# ledboard.net
KiCad netlist of a schematic drawn in EAGLE
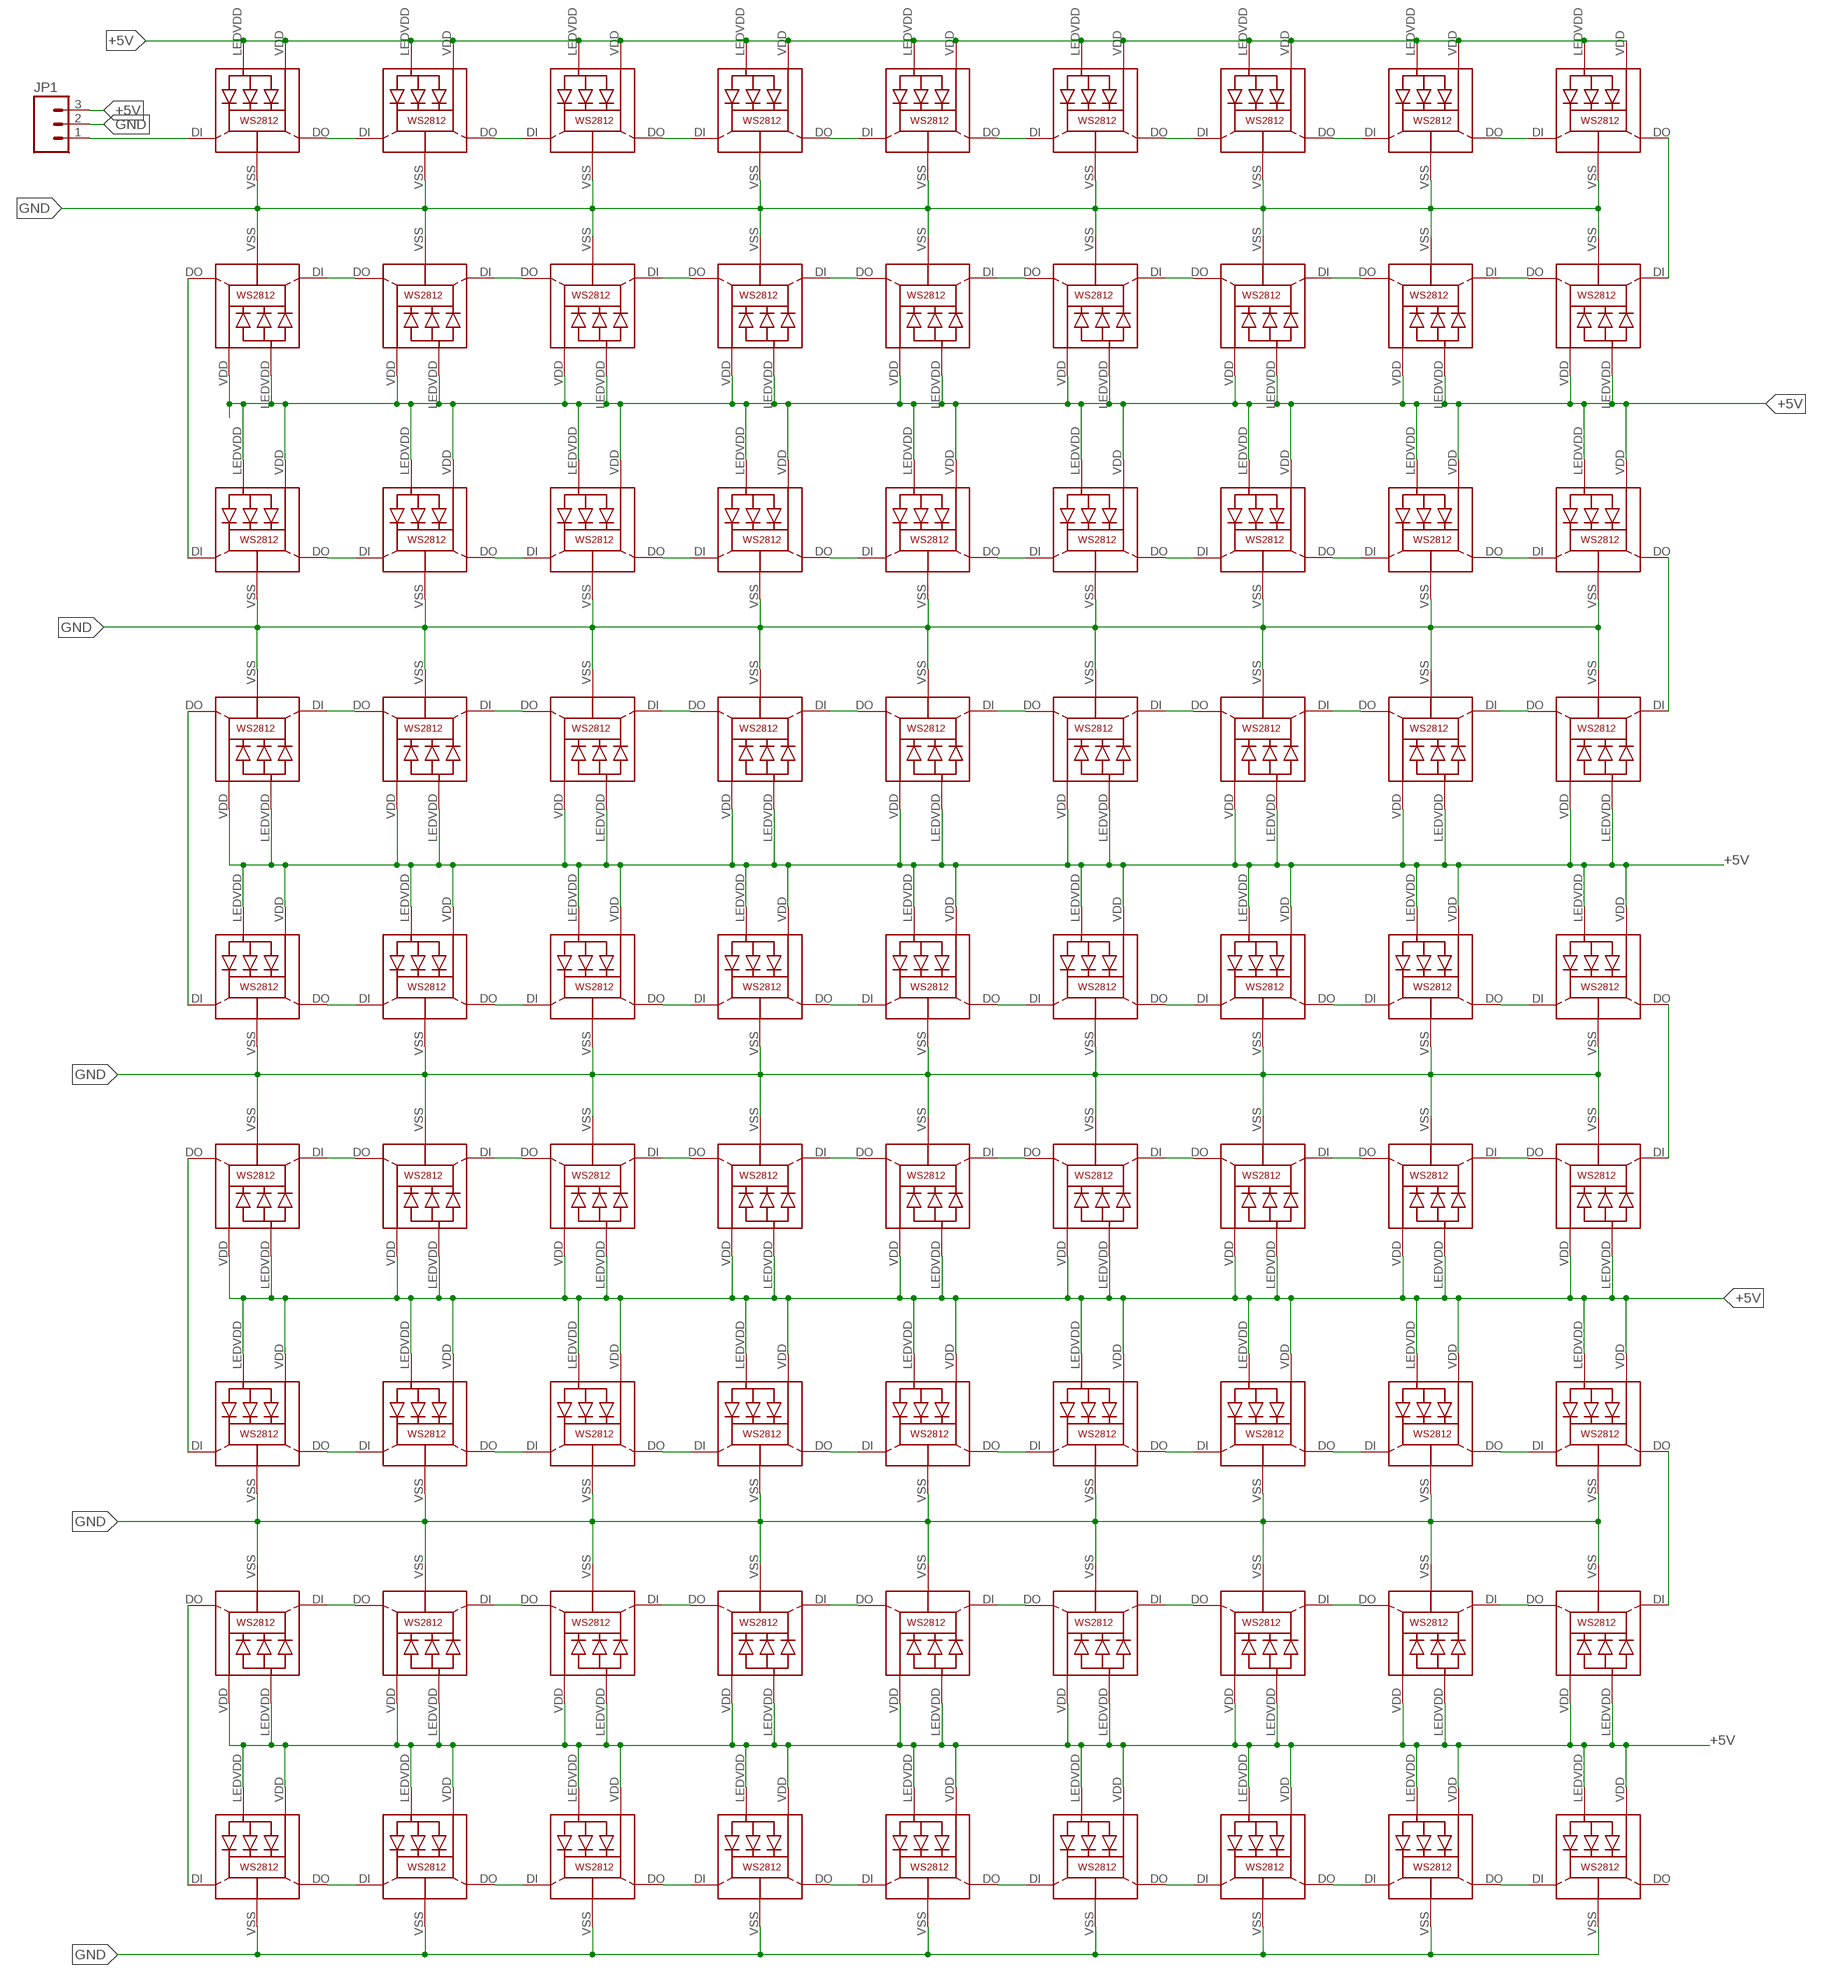
[diagram p0: schematic, sheet 1]

(export (version "E")
  (design (tool "Eeschema 10.0.6"))
  (components
    (comp (ref "JP1")
      (value "M03LONGPADS")
      (footprint "eagle-import:1X03_LONGPADS")
      (libsource (lib "eagle-import") (part "M03LONGPADS"))
    )
    (comp (ref "LEDG00")
      (value "WS2812")
      (footprint "eagle-import:WS2812")
      (libsource (lib "eagle-import") (part "WS2812"))
    )
    (comp (ref "LEDG01")
      (value "WS2812")
      (footprint "eagle-import:WS2812")
      (libsource (lib "eagle-import") (part "WS2812"))
    )
    (comp (ref "LEDG02")
      (value "WS2812")
      (footprint "eagle-import:WS2812")
      (libsource (lib "eagle-import") (part "WS2812"))
    )
    (comp (ref "LEDG03")
      (value "WS2812")
      (footprint "eagle-import:WS2812")
      (libsource (lib "eagle-import") (part "WS2812"))
    )
    (comp (ref "LEDG04")
      (value "WS2812")
      (footprint "eagle-import:WS2812")
      (libsource (lib "eagle-import") (part "WS2812"))
    )
    (comp (ref "LEDG05")
      (value "WS2812")
      (footprint "eagle-import:WS2812")
      (libsource (lib "eagle-import") (part "WS2812"))
    )
    (comp (ref "LEDG06")
      (value "WS2812")
      (footprint "eagle-import:WS2812")
      (libsource (lib "eagle-import") (part "WS2812"))
    )
    (comp (ref "LEDG07")
      (value "WS2812")
      (footprint "eagle-import:WS2812")
      (libsource (lib "eagle-import") (part "WS2812"))
    )
    (comp (ref "LEDG08")
      (value "WS2812")
      (footprint "eagle-import:WS2812")
      (libsource (lib "eagle-import") (part "WS2812"))
    )
    (comp (ref "LEDG10")
      (value "WS2812")
      (footprint "eagle-import:WS2812")
      (libsource (lib "eagle-import") (part "WS2812"))
    )
    (comp (ref "LEDG11")
      (value "WS2812")
      (footprint "eagle-import:WS2812")
      (libsource (lib "eagle-import") (part "WS2812"))
    )
    (comp (ref "LEDG12")
      (value "WS2812")
      (footprint "eagle-import:WS2812")
      (libsource (lib "eagle-import") (part "WS2812"))
    )
    (comp (ref "LEDG13")
      (value "WS2812")
      (footprint "eagle-import:WS2812")
      (libsource (lib "eagle-import") (part "WS2812"))
    )
    (comp (ref "LEDG14")
      (value "WS2812")
      (footprint "eagle-import:WS2812")
      (libsource (lib "eagle-import") (part "WS2812"))
    )
    (comp (ref "LEDG15")
      (value "WS2812")
      (footprint "eagle-import:WS2812")
      (libsource (lib "eagle-import") (part "WS2812"))
    )
    (comp (ref "LEDG16")
      (value "WS2812")
      (footprint "eagle-import:WS2812")
      (libsource (lib "eagle-import") (part "WS2812"))
    )
    (comp (ref "LEDG17")
      (value "WS2812")
      (footprint "eagle-import:WS2812")
      (libsource (lib "eagle-import") (part "WS2812"))
    )
    (comp (ref "LEDG18")
      (value "WS2812")
      (footprint "eagle-import:WS2812")
      (libsource (lib "eagle-import") (part "WS2812"))
    )
    (comp (ref "LEDG20")
      (value "WS2812")
      (footprint "eagle-import:WS2812")
      (libsource (lib "eagle-import") (part "WS2812"))
    )
    (comp (ref "LEDG21")
      (value "WS2812")
      (footprint "eagle-import:WS2812")
      (libsource (lib "eagle-import") (part "WS2812"))
    )
    (comp (ref "LEDG22")
      (value "WS2812")
      (footprint "eagle-import:WS2812")
      (libsource (lib "eagle-import") (part "WS2812"))
    )
    (comp (ref "LEDG23")
      (value "WS2812")
      (footprint "eagle-import:WS2812")
      (libsource (lib "eagle-import") (part "WS2812"))
    )
    (comp (ref "LEDG24")
      (value "WS2812")
      (footprint "eagle-import:WS2812")
      (libsource (lib "eagle-import") (part "WS2812"))
    )
    (comp (ref "LEDG25")
      (value "WS2812")
      (footprint "eagle-import:WS2812")
      (libsource (lib "eagle-import") (part "WS2812"))
    )
    (comp (ref "LEDG26")
      (value "WS2812")
      (footprint "eagle-import:WS2812")
      (libsource (lib "eagle-import") (part "WS2812"))
    )
    (comp (ref "LEDG27")
      (value "WS2812")
      (footprint "eagle-import:WS2812")
      (libsource (lib "eagle-import") (part "WS2812"))
    )
    (comp (ref "LEDG28")
      (value "WS2812")
      (footprint "eagle-import:WS2812")
      (libsource (lib "eagle-import") (part "WS2812"))
    )
    (comp (ref "LEDG30")
      (value "WS2812")
      (footprint "eagle-import:WS2812")
      (libsource (lib "eagle-import") (part "WS2812"))
    )
    (comp (ref "LEDG31")
      (value "WS2812")
      (footprint "eagle-import:WS2812")
      (libsource (lib "eagle-import") (part "WS2812"))
    )
    (comp (ref "LEDG32")
      (value "WS2812")
      (footprint "eagle-import:WS2812")
      (libsource (lib "eagle-import") (part "WS2812"))
    )
    (comp (ref "LEDG33")
      (value "WS2812")
      (footprint "eagle-import:WS2812")
      (libsource (lib "eagle-import") (part "WS2812"))
    )
    (comp (ref "LEDG34")
      (value "WS2812")
      (footprint "eagle-import:WS2812")
      (libsource (lib "eagle-import") (part "WS2812"))
    )
    (comp (ref "LEDG35")
      (value "WS2812")
      (footprint "eagle-import:WS2812")
      (libsource (lib "eagle-import") (part "WS2812"))
    )
    (comp (ref "LEDG36")
      (value "WS2812")
      (footprint "eagle-import:WS2812")
      (libsource (lib "eagle-import") (part "WS2812"))
    )
    (comp (ref "LEDG37")
      (value "WS2812")
      (footprint "eagle-import:WS2812")
      (libsource (lib "eagle-import") (part "WS2812"))
    )
    (comp (ref "LEDG38")
      (value "WS2812")
      (footprint "eagle-import:WS2812")
      (libsource (lib "eagle-import") (part "WS2812"))
    )
    (comp (ref "LEDG40")
      (value "WS2812")
      (footprint "eagle-import:WS2812")
      (libsource (lib "eagle-import") (part "WS2812"))
    )
    (comp (ref "LEDG41")
      (value "WS2812")
      (footprint "eagle-import:WS2812")
      (libsource (lib "eagle-import") (part "WS2812"))
    )
    (comp (ref "LEDG42")
      (value "WS2812")
      (footprint "eagle-import:WS2812")
      (libsource (lib "eagle-import") (part "WS2812"))
    )
    (comp (ref "LEDG43")
      (value "WS2812")
      (footprint "eagle-import:WS2812")
      (libsource (lib "eagle-import") (part "WS2812"))
    )
    (comp (ref "LEDG44")
      (value "WS2812")
      (footprint "eagle-import:WS2812")
      (libsource (lib "eagle-import") (part "WS2812"))
    )
    (comp (ref "LEDG45")
      (value "WS2812")
      (footprint "eagle-import:WS2812")
      (libsource (lib "eagle-import") (part "WS2812"))
    )
    (comp (ref "LEDG46")
      (value "WS2812")
      (footprint "eagle-import:WS2812")
      (libsource (lib "eagle-import") (part "WS2812"))
    )
    (comp (ref "LEDG47")
      (value "WS2812")
      (footprint "eagle-import:WS2812")
      (libsource (lib "eagle-import") (part "WS2812"))
    )
    (comp (ref "LEDG48")
      (value "WS2812")
      (footprint "eagle-import:WS2812")
      (libsource (lib "eagle-import") (part "WS2812"))
    )
    (comp (ref "LEDG50")
      (value "WS2812")
      (footprint "eagle-import:WS2812")
      (libsource (lib "eagle-import") (part "WS2812"))
    )
    (comp (ref "LEDG51")
      (value "WS2812")
      (footprint "eagle-import:WS2812")
      (libsource (lib "eagle-import") (part "WS2812"))
    )
    (comp (ref "LEDG52")
      (value "WS2812")
      (footprint "eagle-import:WS2812")
      (libsource (lib "eagle-import") (part "WS2812"))
    )
    (comp (ref "LEDG53")
      (value "WS2812")
      (footprint "eagle-import:WS2812")
      (libsource (lib "eagle-import") (part "WS2812"))
    )
    (comp (ref "LEDG54")
      (value "WS2812")
      (footprint "eagle-import:WS2812")
      (libsource (lib "eagle-import") (part "WS2812"))
    )
    (comp (ref "LEDG55")
      (value "WS2812")
      (footprint "eagle-import:WS2812")
      (libsource (lib "eagle-import") (part "WS2812"))
    )
    (comp (ref "LEDG56")
      (value "WS2812")
      (footprint "eagle-import:WS2812")
      (libsource (lib "eagle-import") (part "WS2812"))
    )
    (comp (ref "LEDG57")
      (value "WS2812")
      (footprint "eagle-import:WS2812")
      (libsource (lib "eagle-import") (part "WS2812"))
    )
    (comp (ref "LEDG58")
      (value "WS2812")
      (footprint "eagle-import:WS2812")
      (libsource (lib "eagle-import") (part "WS2812"))
    )
    (comp (ref "LEDG60")
      (value "WS2812")
      (footprint "eagle-import:WS2812")
      (libsource (lib "eagle-import") (part "WS2812"))
    )
    (comp (ref "LEDG61")
      (value "WS2812")
      (footprint "eagle-import:WS2812")
      (libsource (lib "eagle-import") (part "WS2812"))
    )
    (comp (ref "LEDG62")
      (value "WS2812")
      (footprint "eagle-import:WS2812")
      (libsource (lib "eagle-import") (part "WS2812"))
    )
    (comp (ref "LEDG63")
      (value "WS2812")
      (footprint "eagle-import:WS2812")
      (libsource (lib "eagle-import") (part "WS2812"))
    )
    (comp (ref "LEDG64")
      (value "WS2812")
      (footprint "eagle-import:WS2812")
      (libsource (lib "eagle-import") (part "WS2812"))
    )
    (comp (ref "LEDG65")
      (value "WS2812")
      (footprint "eagle-import:WS2812")
      (libsource (lib "eagle-import") (part "WS2812"))
    )
    (comp (ref "LEDG66")
      (value "WS2812")
      (footprint "eagle-import:WS2812")
      (libsource (lib "eagle-import") (part "WS2812"))
    )
    (comp (ref "LEDG67")
      (value "WS2812")
      (footprint "eagle-import:WS2812")
      (libsource (lib "eagle-import") (part "WS2812"))
    )
    (comp (ref "LEDG68")
      (value "WS2812")
      (footprint "eagle-import:WS2812")
      (libsource (lib "eagle-import") (part "WS2812"))
    )
    (comp (ref "LEDG70")
      (value "WS2812")
      (footprint "eagle-import:WS2812")
      (libsource (lib "eagle-import") (part "WS2812"))
    )
    (comp (ref "LEDG71")
      (value "WS2812")
      (footprint "eagle-import:WS2812")
      (libsource (lib "eagle-import") (part "WS2812"))
    )
    (comp (ref "LEDG72")
      (value "WS2812")
      (footprint "eagle-import:WS2812")
      (libsource (lib "eagle-import") (part "WS2812"))
    )
    (comp (ref "LEDG73")
      (value "WS2812")
      (footprint "eagle-import:WS2812")
      (libsource (lib "eagle-import") (part "WS2812"))
    )
    (comp (ref "LEDG74")
      (value "WS2812")
      (footprint "eagle-import:WS2812")
      (libsource (lib "eagle-import") (part "WS2812"))
    )
    (comp (ref "LEDG75")
      (value "WS2812")
      (footprint "eagle-import:WS2812")
      (libsource (lib "eagle-import") (part "WS2812"))
    )
    (comp (ref "LEDG76")
      (value "WS2812")
      (footprint "eagle-import:WS2812")
      (libsource (lib "eagle-import") (part "WS2812"))
    )
    (comp (ref "LEDG77")
      (value "WS2812")
      (footprint "eagle-import:WS2812")
      (libsource (lib "eagle-import") (part "WS2812"))
    )
    (comp (ref "LEDG78")
      (value "WS2812")
      (footprint "eagle-import:WS2812")
      (libsource (lib "eagle-import") (part "WS2812"))
    )
    (comp (ref "LEDG80")
      (value "WS2812")
      (footprint "eagle-import:WS2812")
      (libsource (lib "eagle-import") (part "WS2812"))
    )
    (comp (ref "LEDG81")
      (value "WS2812")
      (footprint "eagle-import:WS2812")
      (libsource (lib "eagle-import") (part "WS2812"))
    )
    (comp (ref "LEDG82")
      (value "WS2812")
      (footprint "eagle-import:WS2812")
      (libsource (lib "eagle-import") (part "WS2812"))
    )
    (comp (ref "LEDG83")
      (value "WS2812")
      (footprint "eagle-import:WS2812")
      (libsource (lib "eagle-import") (part "WS2812"))
    )
    (comp (ref "LEDG84")
      (value "WS2812")
      (footprint "eagle-import:WS2812")
      (libsource (lib "eagle-import") (part "WS2812"))
    )
    (comp (ref "LEDG85")
      (value "WS2812")
      (footprint "eagle-import:WS2812")
      (libsource (lib "eagle-import") (part "WS2812"))
    )
    (comp (ref "LEDG86")
      (value "WS2812")
      (footprint "eagle-import:WS2812")
      (libsource (lib "eagle-import") (part "WS2812"))
    )
    (comp (ref "LEDG87")
      (value "WS2812")
      (footprint "eagle-import:WS2812")
      (libsource (lib "eagle-import") (part "WS2812"))
    )
    (comp (ref "LEDG88")
      (value "WS2812")
      (footprint "eagle-import:WS2812")
      (libsource (lib "eagle-import") (part "WS2812"))
    )
  )
  (nets
    (net (code "1") (name "+5V") (class "Default")
      (node (ref "JP1") (pin "3") (pinfunction "3_3") (pintype "passive"))
      (node (ref "LEDG00") (pin "LEDVDD") (pinfunction "LEDVDD_LEDVDD") (pintype "power_in"))
      (node (ref "LEDG00") (pin "VDD") (pinfunction "VDD_VDD") (pintype "power_in"))
      (node (ref "LEDG01") (pin "LEDVDD") (pinfunction "LEDVDD_LEDVDD") (pintype "power_in"))
      (node (ref "LEDG01") (pin "VDD") (pinfunction "VDD_VDD") (pintype "power_in"))
      (node (ref "LEDG02") (pin "LEDVDD") (pinfunction "LEDVDD_LEDVDD") (pintype "power_in"))
      (node (ref "LEDG02") (pin "VDD") (pinfunction "VDD_VDD") (pintype "power_in"))
      (node (ref "LEDG03") (pin "LEDVDD") (pinfunction "LEDVDD_LEDVDD") (pintype "power_in"))
      (node (ref "LEDG03") (pin "VDD") (pinfunction "VDD_VDD") (pintype "power_in"))
      (node (ref "LEDG04") (pin "LEDVDD") (pinfunction "LEDVDD_LEDVDD") (pintype "power_in"))
      (node (ref "LEDG04") (pin "VDD") (pinfunction "VDD_VDD") (pintype "power_in"))
      (node (ref "LEDG05") (pin "LEDVDD") (pinfunction "LEDVDD_LEDVDD") (pintype "power_in"))
      (node (ref "LEDG05") (pin "VDD") (pinfunction "VDD_VDD") (pintype "power_in"))
      (node (ref "LEDG06") (pin "LEDVDD") (pinfunction "LEDVDD_LEDVDD") (pintype "power_in"))
      (node (ref "LEDG06") (pin "VDD") (pinfunction "VDD_VDD") (pintype "power_in"))
      (node (ref "LEDG07") (pin "LEDVDD") (pinfunction "LEDVDD_LEDVDD") (pintype "power_in"))
      (node (ref "LEDG07") (pin "VDD") (pinfunction "VDD_VDD") (pintype "power_in"))
      (node (ref "LEDG08") (pin "LEDVDD") (pinfunction "LEDVDD_LEDVDD") (pintype "power_in"))
      (node (ref "LEDG08") (pin "VDD") (pinfunction "VDD_VDD") (pintype "power_in"))
      (node (ref "LEDG10") (pin "LEDVDD") (pinfunction "LEDVDD_LEDVDD") (pintype "power_in"))
      (node (ref "LEDG10") (pin "VDD") (pinfunction "VDD_VDD") (pintype "power_in"))
      (node (ref "LEDG11") (pin "LEDVDD") (pinfunction "LEDVDD_LEDVDD") (pintype "power_in"))
      (node (ref "LEDG11") (pin "VDD") (pinfunction "VDD_VDD") (pintype "power_in"))
      (node (ref "LEDG12") (pin "LEDVDD") (pinfunction "LEDVDD_LEDVDD") (pintype "power_in"))
      (node (ref "LEDG12") (pin "VDD") (pinfunction "VDD_VDD") (pintype "power_in"))
      (node (ref "LEDG13") (pin "LEDVDD") (pinfunction "LEDVDD_LEDVDD") (pintype "power_in"))
      (node (ref "LEDG13") (pin "VDD") (pinfunction "VDD_VDD") (pintype "power_in"))
      (node (ref "LEDG14") (pin "LEDVDD") (pinfunction "LEDVDD_LEDVDD") (pintype "power_in"))
      (node (ref "LEDG14") (pin "VDD") (pinfunction "VDD_VDD") (pintype "power_in"))
      (node (ref "LEDG15") (pin "LEDVDD") (pinfunction "LEDVDD_LEDVDD") (pintype "power_in"))
      (node (ref "LEDG15") (pin "VDD") (pinfunction "VDD_VDD") (pintype "power_in"))
      (node (ref "LEDG16") (pin "LEDVDD") (pinfunction "LEDVDD_LEDVDD") (pintype "power_in"))
      (node (ref "LEDG16") (pin "VDD") (pinfunction "VDD_VDD") (pintype "power_in"))
      (node (ref "LEDG17") (pin "LEDVDD") (pinfunction "LEDVDD_LEDVDD") (pintype "power_in"))
      (node (ref "LEDG17") (pin "VDD") (pinfunction "VDD_VDD") (pintype "power_in"))
      (node (ref "LEDG18") (pin "LEDVDD") (pinfunction "LEDVDD_LEDVDD") (pintype "power_in"))
      (node (ref "LEDG18") (pin "VDD") (pinfunction "VDD_VDD") (pintype "power_in"))
      (node (ref "LEDG20") (pin "LEDVDD") (pinfunction "LEDVDD_LEDVDD") (pintype "power_in"))
      (node (ref "LEDG20") (pin "VDD") (pinfunction "VDD_VDD") (pintype "power_in"))
      (node (ref "LEDG21") (pin "LEDVDD") (pinfunction "LEDVDD_LEDVDD") (pintype "power_in"))
      (node (ref "LEDG21") (pin "VDD") (pinfunction "VDD_VDD") (pintype "power_in"))
      (node (ref "LEDG22") (pin "LEDVDD") (pinfunction "LEDVDD_LEDVDD") (pintype "power_in"))
      (node (ref "LEDG22") (pin "VDD") (pinfunction "VDD_VDD") (pintype "power_in"))
      (node (ref "LEDG23") (pin "LEDVDD") (pinfunction "LEDVDD_LEDVDD") (pintype "power_in"))
      (node (ref "LEDG23") (pin "VDD") (pinfunction "VDD_VDD") (pintype "power_in"))
      (node (ref "LEDG24") (pin "LEDVDD") (pinfunction "LEDVDD_LEDVDD") (pintype "power_in"))
      (node (ref "LEDG24") (pin "VDD") (pinfunction "VDD_VDD") (pintype "power_in"))
      (node (ref "LEDG25") (pin "LEDVDD") (pinfunction "LEDVDD_LEDVDD") (pintype "power_in"))
      (node (ref "LEDG25") (pin "VDD") (pinfunction "VDD_VDD") (pintype "power_in"))
      (node (ref "LEDG26") (pin "LEDVDD") (pinfunction "LEDVDD_LEDVDD") (pintype "power_in"))
      (node (ref "LEDG26") (pin "VDD") (pinfunction "VDD_VDD") (pintype "power_in"))
      (node (ref "LEDG27") (pin "LEDVDD") (pinfunction "LEDVDD_LEDVDD") (pintype "power_in"))
      (node (ref "LEDG27") (pin "VDD") (pinfunction "VDD_VDD") (pintype "power_in"))
      (node (ref "LEDG28") (pin "LEDVDD") (pinfunction "LEDVDD_LEDVDD") (pintype "power_in"))
      (node (ref "LEDG28") (pin "VDD") (pinfunction "VDD_VDD") (pintype "power_in"))
      (node (ref "LEDG30") (pin "LEDVDD") (pinfunction "LEDVDD_LEDVDD") (pintype "power_in"))
      (node (ref "LEDG30") (pin "VDD") (pinfunction "VDD_VDD") (pintype "power_in"))
      (node (ref "LEDG31") (pin "LEDVDD") (pinfunction "LEDVDD_LEDVDD") (pintype "power_in"))
      (node (ref "LEDG31") (pin "VDD") (pinfunction "VDD_VDD") (pintype "power_in"))
      (node (ref "LEDG32") (pin "LEDVDD") (pinfunction "LEDVDD_LEDVDD") (pintype "power_in"))
      (node (ref "LEDG32") (pin "VDD") (pinfunction "VDD_VDD") (pintype "power_in"))
      (node (ref "LEDG33") (pin "LEDVDD") (pinfunction "LEDVDD_LEDVDD") (pintype "power_in"))
      (node (ref "LEDG33") (pin "VDD") (pinfunction "VDD_VDD") (pintype "power_in"))
      (node (ref "LEDG34") (pin "LEDVDD") (pinfunction "LEDVDD_LEDVDD") (pintype "power_in"))
      (node (ref "LEDG34") (pin "VDD") (pinfunction "VDD_VDD") (pintype "power_in"))
      (node (ref "LEDG35") (pin "LEDVDD") (pinfunction "LEDVDD_LEDVDD") (pintype "power_in"))
      (node (ref "LEDG35") (pin "VDD") (pinfunction "VDD_VDD") (pintype "power_in"))
      (node (ref "LEDG36") (pin "LEDVDD") (pinfunction "LEDVDD_LEDVDD") (pintype "power_in"))
      (node (ref "LEDG36") (pin "VDD") (pinfunction "VDD_VDD") (pintype "power_in"))
      (node (ref "LEDG37") (pin "LEDVDD") (pinfunction "LEDVDD_LEDVDD") (pintype "power_in"))
      (node (ref "LEDG37") (pin "VDD") (pinfunction "VDD_VDD") (pintype "power_in"))
      (node (ref "LEDG38") (pin "LEDVDD") (pinfunction "LEDVDD_LEDVDD") (pintype "power_in"))
      (node (ref "LEDG38") (pin "VDD") (pinfunction "VDD_VDD") (pintype "power_in"))
      (node (ref "LEDG40") (pin "LEDVDD") (pinfunction "LEDVDD_LEDVDD") (pintype "power_in"))
      (node (ref "LEDG40") (pin "VDD") (pinfunction "VDD_VDD") (pintype "power_in"))
      (node (ref "LEDG41") (pin "LEDVDD") (pinfunction "LEDVDD_LEDVDD") (pintype "power_in"))
      (node (ref "LEDG41") (pin "VDD") (pinfunction "VDD_VDD") (pintype "power_in"))
      (node (ref "LEDG42") (pin "LEDVDD") (pinfunction "LEDVDD_LEDVDD") (pintype "power_in"))
      (node (ref "LEDG42") (pin "VDD") (pinfunction "VDD_VDD") (pintype "power_in"))
      (node (ref "LEDG43") (pin "LEDVDD") (pinfunction "LEDVDD_LEDVDD") (pintype "power_in"))
      (node (ref "LEDG43") (pin "VDD") (pinfunction "VDD_VDD") (pintype "power_in"))
      (node (ref "LEDG44") (pin "LEDVDD") (pinfunction "LEDVDD_LEDVDD") (pintype "power_in"))
      (node (ref "LEDG44") (pin "VDD") (pinfunction "VDD_VDD") (pintype "power_in"))
      (node (ref "LEDG45") (pin "LEDVDD") (pinfunction "LEDVDD_LEDVDD") (pintype "power_in"))
      (node (ref "LEDG45") (pin "VDD") (pinfunction "VDD_VDD") (pintype "power_in"))
      (node (ref "LEDG46") (pin "LEDVDD") (pinfunction "LEDVDD_LEDVDD") (pintype "power_in"))
      (node (ref "LEDG46") (pin "VDD") (pinfunction "VDD_VDD") (pintype "power_in"))
      (node (ref "LEDG47") (pin "LEDVDD") (pinfunction "LEDVDD_LEDVDD") (pintype "power_in"))
      (node (ref "LEDG47") (pin "VDD") (pinfunction "VDD_VDD") (pintype "power_in"))
      (node (ref "LEDG48") (pin "LEDVDD") (pinfunction "LEDVDD_LEDVDD") (pintype "power_in"))
      (node (ref "LEDG48") (pin "VDD") (pinfunction "VDD_VDD") (pintype "power_in"))
      (node (ref "LEDG50") (pin "LEDVDD") (pinfunction "LEDVDD_LEDVDD") (pintype "power_in"))
      (node (ref "LEDG50") (pin "VDD") (pinfunction "VDD_VDD") (pintype "power_in"))
      (node (ref "LEDG51") (pin "LEDVDD") (pinfunction "LEDVDD_LEDVDD") (pintype "power_in"))
      (node (ref "LEDG51") (pin "VDD") (pinfunction "VDD_VDD") (pintype "power_in"))
      (node (ref "LEDG52") (pin "LEDVDD") (pinfunction "LEDVDD_LEDVDD") (pintype "power_in"))
      (node (ref "LEDG52") (pin "VDD") (pinfunction "VDD_VDD") (pintype "power_in"))
      (node (ref "LEDG53") (pin "LEDVDD") (pinfunction "LEDVDD_LEDVDD") (pintype "power_in"))
      (node (ref "LEDG53") (pin "VDD") (pinfunction "VDD_VDD") (pintype "power_in"))
      (node (ref "LEDG54") (pin "LEDVDD") (pinfunction "LEDVDD_LEDVDD") (pintype "power_in"))
      (node (ref "LEDG54") (pin "VDD") (pinfunction "VDD_VDD") (pintype "power_in"))
      (node (ref "LEDG55") (pin "LEDVDD") (pinfunction "LEDVDD_LEDVDD") (pintype "power_in"))
      (node (ref "LEDG55") (pin "VDD") (pinfunction "VDD_VDD") (pintype "power_in"))
      (node (ref "LEDG56") (pin "LEDVDD") (pinfunction "LEDVDD_LEDVDD") (pintype "power_in"))
      (node (ref "LEDG56") (pin "VDD") (pinfunction "VDD_VDD") (pintype "power_in"))
      (node (ref "LEDG57") (pin "LEDVDD") (pinfunction "LEDVDD_LEDVDD") (pintype "power_in"))
      (node (ref "LEDG57") (pin "VDD") (pinfunction "VDD_VDD") (pintype "power_in"))
      (node (ref "LEDG58") (pin "LEDVDD") (pinfunction "LEDVDD_LEDVDD") (pintype "power_in"))
      (node (ref "LEDG58") (pin "VDD") (pinfunction "VDD_VDD") (pintype "power_in"))
      (node (ref "LEDG60") (pin "LEDVDD") (pinfunction "LEDVDD_LEDVDD") (pintype "power_in"))
      (node (ref "LEDG60") (pin "VDD") (pinfunction "VDD_VDD") (pintype "power_in"))
      (node (ref "LEDG61") (pin "LEDVDD") (pinfunction "LEDVDD_LEDVDD") (pintype "power_in"))
      (node (ref "LEDG61") (pin "VDD") (pinfunction "VDD_VDD") (pintype "power_in"))
      (node (ref "LEDG62") (pin "LEDVDD") (pinfunction "LEDVDD_LEDVDD") (pintype "power_in"))
      (node (ref "LEDG62") (pin "VDD") (pinfunction "VDD_VDD") (pintype "power_in"))
      (node (ref "LEDG63") (pin "LEDVDD") (pinfunction "LEDVDD_LEDVDD") (pintype "power_in"))
      (node (ref "LEDG63") (pin "VDD") (pinfunction "VDD_VDD") (pintype "power_in"))
      (node (ref "LEDG64") (pin "LEDVDD") (pinfunction "LEDVDD_LEDVDD") (pintype "power_in"))
      (node (ref "LEDG64") (pin "VDD") (pinfunction "VDD_VDD") (pintype "power_in"))
      (node (ref "LEDG65") (pin "LEDVDD") (pinfunction "LEDVDD_LEDVDD") (pintype "power_in"))
      (node (ref "LEDG65") (pin "VDD") (pinfunction "VDD_VDD") (pintype "power_in"))
      (node (ref "LEDG66") (pin "LEDVDD") (pinfunction "LEDVDD_LEDVDD") (pintype "power_in"))
      (node (ref "LEDG66") (pin "VDD") (pinfunction "VDD_VDD") (pintype "power_in"))
      (node (ref "LEDG67") (pin "LEDVDD") (pinfunction "LEDVDD_LEDVDD") (pintype "power_in"))
      (node (ref "LEDG67") (pin "VDD") (pinfunction "VDD_VDD") (pintype "power_in"))
      (node (ref "LEDG68") (pin "LEDVDD") (pinfunction "LEDVDD_LEDVDD") (pintype "power_in"))
      (node (ref "LEDG68") (pin "VDD") (pinfunction "VDD_VDD") (pintype "power_in"))
      (node (ref "LEDG70") (pin "LEDVDD") (pinfunction "LEDVDD_LEDVDD") (pintype "power_in"))
      (node (ref "LEDG70") (pin "VDD") (pinfunction "VDD_VDD") (pintype "power_in"))
      (node (ref "LEDG71") (pin "LEDVDD") (pinfunction "LEDVDD_LEDVDD") (pintype "power_in"))
      (node (ref "LEDG71") (pin "VDD") (pinfunction "VDD_VDD") (pintype "power_in"))
      (node (ref "LEDG72") (pin "LEDVDD") (pinfunction "LEDVDD_LEDVDD") (pintype "power_in"))
      (node (ref "LEDG72") (pin "VDD") (pinfunction "VDD_VDD") (pintype "power_in"))
      (node (ref "LEDG73") (pin "LEDVDD") (pinfunction "LEDVDD_LEDVDD") (pintype "power_in"))
      (node (ref "LEDG73") (pin "VDD") (pinfunction "VDD_VDD") (pintype "power_in"))
      (node (ref "LEDG74") (pin "LEDVDD") (pinfunction "LEDVDD_LEDVDD") (pintype "power_in"))
      (node (ref "LEDG74") (pin "VDD") (pinfunction "VDD_VDD") (pintype "power_in"))
      (node (ref "LEDG75") (pin "LEDVDD") (pinfunction "LEDVDD_LEDVDD") (pintype "power_in"))
      (node (ref "LEDG75") (pin "VDD") (pinfunction "VDD_VDD") (pintype "power_in"))
      (node (ref "LEDG76") (pin "LEDVDD") (pinfunction "LEDVDD_LEDVDD") (pintype "power_in"))
      (node (ref "LEDG76") (pin "VDD") (pinfunction "VDD_VDD") (pintype "power_in"))
      (node (ref "LEDG77") (pin "LEDVDD") (pinfunction "LEDVDD_LEDVDD") (pintype "power_in"))
      (node (ref "LEDG77") (pin "VDD") (pinfunction "VDD_VDD") (pintype "power_in"))
      (node (ref "LEDG78") (pin "LEDVDD") (pinfunction "LEDVDD_LEDVDD") (pintype "power_in"))
      (node (ref "LEDG78") (pin "VDD") (pinfunction "VDD_VDD") (pintype "power_in"))
      (node (ref "LEDG80") (pin "LEDVDD") (pinfunction "LEDVDD_LEDVDD") (pintype "power_in"))
      (node (ref "LEDG80") (pin "VDD") (pinfunction "VDD_VDD") (pintype "power_in"))
      (node (ref "LEDG81") (pin "LEDVDD") (pinfunction "LEDVDD_LEDVDD") (pintype "power_in"))
      (node (ref "LEDG81") (pin "VDD") (pinfunction "VDD_VDD") (pintype "power_in"))
      (node (ref "LEDG82") (pin "LEDVDD") (pinfunction "LEDVDD_LEDVDD") (pintype "power_in"))
      (node (ref "LEDG82") (pin "VDD") (pinfunction "VDD_VDD") (pintype "power_in"))
      (node (ref "LEDG83") (pin "LEDVDD") (pinfunction "LEDVDD_LEDVDD") (pintype "power_in"))
      (node (ref "LEDG83") (pin "VDD") (pinfunction "VDD_VDD") (pintype "power_in"))
      (node (ref "LEDG84") (pin "LEDVDD") (pinfunction "LEDVDD_LEDVDD") (pintype "power_in"))
      (node (ref "LEDG84") (pin "VDD") (pinfunction "VDD_VDD") (pintype "power_in"))
      (node (ref "LEDG85") (pin "LEDVDD") (pinfunction "LEDVDD_LEDVDD") (pintype "power_in"))
      (node (ref "LEDG85") (pin "VDD") (pinfunction "VDD_VDD") (pintype "power_in"))
      (node (ref "LEDG86") (pin "LEDVDD") (pinfunction "LEDVDD_LEDVDD") (pintype "power_in"))
      (node (ref "LEDG86") (pin "VDD") (pinfunction "VDD_VDD") (pintype "power_in"))
      (node (ref "LEDG87") (pin "LEDVDD") (pinfunction "LEDVDD_LEDVDD") (pintype "power_in"))
      (node (ref "LEDG87") (pin "VDD") (pinfunction "VDD_VDD") (pintype "power_in"))
      (node (ref "LEDG88") (pin "LEDVDD") (pinfunction "LEDVDD_LEDVDD") (pintype "power_in"))
      (node (ref "LEDG88") (pin "VDD") (pinfunction "VDD_VDD") (pintype "power_in"))
    )
    (net (code "2") (name "GND") (class "Default")
      (node (ref "JP1") (pin "2") (pinfunction "2_2") (pintype "passive"))
      (node (ref "LEDG00") (pin "VSS") (pinfunction "GND_VSS") (pintype "power_in"))
      (node (ref "LEDG01") (pin "VSS") (pinfunction "GND_VSS") (pintype "power_in"))
      (node (ref "LEDG02") (pin "VSS") (pinfunction "GND_VSS") (pintype "power_in"))
      (node (ref "LEDG03") (pin "VSS") (pinfunction "GND_VSS") (pintype "power_in"))
      (node (ref "LEDG04") (pin "VSS") (pinfunction "GND_VSS") (pintype "power_in"))
      (node (ref "LEDG05") (pin "VSS") (pinfunction "GND_VSS") (pintype "power_in"))
      (node (ref "LEDG06") (pin "VSS") (pinfunction "GND_VSS") (pintype "power_in"))
      (node (ref "LEDG07") (pin "VSS") (pinfunction "GND_VSS") (pintype "power_in"))
      (node (ref "LEDG08") (pin "VSS") (pinfunction "GND_VSS") (pintype "power_in"))
      (node (ref "LEDG10") (pin "VSS") (pinfunction "GND_VSS") (pintype "power_in"))
      (node (ref "LEDG11") (pin "VSS") (pinfunction "GND_VSS") (pintype "power_in"))
      (node (ref "LEDG12") (pin "VSS") (pinfunction "GND_VSS") (pintype "power_in"))
      (node (ref "LEDG13") (pin "VSS") (pinfunction "GND_VSS") (pintype "power_in"))
      (node (ref "LEDG14") (pin "VSS") (pinfunction "GND_VSS") (pintype "power_in"))
      (node (ref "LEDG15") (pin "VSS") (pinfunction "GND_VSS") (pintype "power_in"))
      (node (ref "LEDG16") (pin "VSS") (pinfunction "GND_VSS") (pintype "power_in"))
      (node (ref "LEDG17") (pin "VSS") (pinfunction "GND_VSS") (pintype "power_in"))
      (node (ref "LEDG18") (pin "VSS") (pinfunction "GND_VSS") (pintype "power_in"))
      (node (ref "LEDG20") (pin "VSS") (pinfunction "GND_VSS") (pintype "power_in"))
      (node (ref "LEDG21") (pin "VSS") (pinfunction "GND_VSS") (pintype "power_in"))
      (node (ref "LEDG22") (pin "VSS") (pinfunction "GND_VSS") (pintype "power_in"))
      (node (ref "LEDG23") (pin "VSS") (pinfunction "GND_VSS") (pintype "power_in"))
      (node (ref "LEDG24") (pin "VSS") (pinfunction "GND_VSS") (pintype "power_in"))
      (node (ref "LEDG25") (pin "VSS") (pinfunction "GND_VSS") (pintype "power_in"))
      (node (ref "LEDG26") (pin "VSS") (pinfunction "GND_VSS") (pintype "power_in"))
      (node (ref "LEDG27") (pin "VSS") (pinfunction "GND_VSS") (pintype "power_in"))
      (node (ref "LEDG28") (pin "VSS") (pinfunction "GND_VSS") (pintype "power_in"))
      (node (ref "LEDG30") (pin "VSS") (pinfunction "GND_VSS") (pintype "power_in"))
      (node (ref "LEDG31") (pin "VSS") (pinfunction "GND_VSS") (pintype "power_in"))
      (node (ref "LEDG32") (pin "VSS") (pinfunction "GND_VSS") (pintype "power_in"))
      (node (ref "LEDG33") (pin "VSS") (pinfunction "GND_VSS") (pintype "power_in"))
      (node (ref "LEDG34") (pin "VSS") (pinfunction "GND_VSS") (pintype "power_in"))
      (node (ref "LEDG35") (pin "VSS") (pinfunction "GND_VSS") (pintype "power_in"))
      (node (ref "LEDG36") (pin "VSS") (pinfunction "GND_VSS") (pintype "power_in"))
      (node (ref "LEDG37") (pin "VSS") (pinfunction "GND_VSS") (pintype "power_in"))
      (node (ref "LEDG38") (pin "VSS") (pinfunction "GND_VSS") (pintype "power_in"))
      (node (ref "LEDG40") (pin "VSS") (pinfunction "GND_VSS") (pintype "power_in"))
      (node (ref "LEDG41") (pin "VSS") (pinfunction "GND_VSS") (pintype "power_in"))
      (node (ref "LEDG42") (pin "VSS") (pinfunction "GND_VSS") (pintype "power_in"))
      (node (ref "LEDG43") (pin "VSS") (pinfunction "GND_VSS") (pintype "power_in"))
      (node (ref "LEDG44") (pin "VSS") (pinfunction "GND_VSS") (pintype "power_in"))
      (node (ref "LEDG45") (pin "VSS") (pinfunction "GND_VSS") (pintype "power_in"))
      (node (ref "LEDG46") (pin "VSS") (pinfunction "GND_VSS") (pintype "power_in"))
      (node (ref "LEDG47") (pin "VSS") (pinfunction "GND_VSS") (pintype "power_in"))
      (node (ref "LEDG48") (pin "VSS") (pinfunction "GND_VSS") (pintype "power_in"))
      (node (ref "LEDG50") (pin "VSS") (pinfunction "GND_VSS") (pintype "power_in"))
      (node (ref "LEDG51") (pin "VSS") (pinfunction "GND_VSS") (pintype "power_in"))
      (node (ref "LEDG52") (pin "VSS") (pinfunction "GND_VSS") (pintype "power_in"))
      (node (ref "LEDG53") (pin "VSS") (pinfunction "GND_VSS") (pintype "power_in"))
      (node (ref "LEDG54") (pin "VSS") (pinfunction "GND_VSS") (pintype "power_in"))
      (node (ref "LEDG55") (pin "VSS") (pinfunction "GND_VSS") (pintype "power_in"))
      (node (ref "LEDG56") (pin "VSS") (pinfunction "GND_VSS") (pintype "power_in"))
      (node (ref "LEDG57") (pin "VSS") (pinfunction "GND_VSS") (pintype "power_in"))
      (node (ref "LEDG58") (pin "VSS") (pinfunction "GND_VSS") (pintype "power_in"))
      (node (ref "LEDG60") (pin "VSS") (pinfunction "GND_VSS") (pintype "power_in"))
      (node (ref "LEDG61") (pin "VSS") (pinfunction "GND_VSS") (pintype "power_in"))
      (node (ref "LEDG62") (pin "VSS") (pinfunction "GND_VSS") (pintype "power_in"))
      (node (ref "LEDG63") (pin "VSS") (pinfunction "GND_VSS") (pintype "power_in"))
      (node (ref "LEDG64") (pin "VSS") (pinfunction "GND_VSS") (pintype "power_in"))
      (node (ref "LEDG65") (pin "VSS") (pinfunction "GND_VSS") (pintype "power_in"))
      (node (ref "LEDG66") (pin "VSS") (pinfunction "GND_VSS") (pintype "power_in"))
      (node (ref "LEDG67") (pin "VSS") (pinfunction "GND_VSS") (pintype "power_in"))
      (node (ref "LEDG68") (pin "VSS") (pinfunction "GND_VSS") (pintype "power_in"))
      (node (ref "LEDG70") (pin "VSS") (pinfunction "GND_VSS") (pintype "power_in"))
      (node (ref "LEDG71") (pin "VSS") (pinfunction "GND_VSS") (pintype "power_in"))
      (node (ref "LEDG72") (pin "VSS") (pinfunction "GND_VSS") (pintype "power_in"))
      (node (ref "LEDG73") (pin "VSS") (pinfunction "GND_VSS") (pintype "power_in"))
      (node (ref "LEDG74") (pin "VSS") (pinfunction "GND_VSS") (pintype "power_in"))
      (node (ref "LEDG75") (pin "VSS") (pinfunction "GND_VSS") (pintype "power_in"))
      (node (ref "LEDG76") (pin "VSS") (pinfunction "GND_VSS") (pintype "power_in"))
      (node (ref "LEDG77") (pin "VSS") (pinfunction "GND_VSS") (pintype "power_in"))
      (node (ref "LEDG78") (pin "VSS") (pinfunction "GND_VSS") (pintype "power_in"))
      (node (ref "LEDG80") (pin "VSS") (pinfunction "GND_VSS") (pintype "power_in"))
      (node (ref "LEDG81") (pin "VSS") (pinfunction "GND_VSS") (pintype "power_in"))
      (node (ref "LEDG82") (pin "VSS") (pinfunction "GND_VSS") (pintype "power_in"))
      (node (ref "LEDG83") (pin "VSS") (pinfunction "GND_VSS") (pintype "power_in"))
      (node (ref "LEDG84") (pin "VSS") (pinfunction "GND_VSS") (pintype "power_in"))
      (node (ref "LEDG85") (pin "VSS") (pinfunction "GND_VSS") (pintype "power_in"))
      (node (ref "LEDG86") (pin "VSS") (pinfunction "GND_VSS") (pintype "power_in"))
      (node (ref "LEDG87") (pin "VSS") (pinfunction "GND_VSS") (pintype "power_in"))
      (node (ref "LEDG88") (pin "VSS") (pinfunction "GND_VSS") (pintype "power_in"))
    )
    (net (code "3") (name "Net-(JP1-Pad1)") (class "Default")
      (node (ref "JP1") (pin "1") (pinfunction "1_1") (pintype "passive"))
      (node (ref "LEDG00") (pin "DI") (pinfunction "DI_DI") (pintype "input"))
    )
    (net (code "4") (name "Net-(LEDG00-PadDO)") (class "Default")
      (node (ref "LEDG00") (pin "DO") (pinfunction "DO_DO") (pintype "output"))
      (node (ref "LEDG10") (pin "DI") (pinfunction "DI_DI") (pintype "input"))
    )
    (net (code "5") (name "Net-(LEDG01-PadDI)") (class "Default")
      (node (ref "LEDG01") (pin "DI") (pinfunction "DI_DI") (pintype "input"))
      (node (ref "LEDG11") (pin "DO") (pinfunction "DO_DO") (pintype "output"))
    )
    (net (code "6") (name "Net-(LEDG01-PadDO)") (class "Default")
      (node (ref "LEDG01") (pin "DO") (pinfunction "DO_DO") (pintype "output"))
      (node (ref "LEDG02") (pin "DI") (pinfunction "DI_DI") (pintype "input"))
    )
    (net (code "7") (name "Net-(LEDG02-PadDO)") (class "Default")
      (node (ref "LEDG02") (pin "DO") (pinfunction "DO_DO") (pintype "output"))
      (node (ref "LEDG12") (pin "DI") (pinfunction "DI_DI") (pintype "input"))
    )
    (net (code "8") (name "Net-(LEDG03-PadDI)") (class "Default")
      (node (ref "LEDG03") (pin "DI") (pinfunction "DI_DI") (pintype "input"))
      (node (ref "LEDG13") (pin "DO") (pinfunction "DO_DO") (pintype "output"))
    )
    (net (code "9") (name "Net-(LEDG03-PadDO)") (class "Default")
      (node (ref "LEDG03") (pin "DO") (pinfunction "DO_DO") (pintype "output"))
      (node (ref "LEDG04") (pin "DI") (pinfunction "DI_DI") (pintype "input"))
    )
    (net (code "10") (name "Net-(LEDG04-PadDO)") (class "Default")
      (node (ref "LEDG04") (pin "DO") (pinfunction "DO_DO") (pintype "output"))
      (node (ref "LEDG14") (pin "DI") (pinfunction "DI_DI") (pintype "input"))
    )
    (net (code "11") (name "Net-(LEDG05-PadDI)") (class "Default")
      (node (ref "LEDG05") (pin "DI") (pinfunction "DI_DI") (pintype "input"))
      (node (ref "LEDG15") (pin "DO") (pinfunction "DO_DO") (pintype "output"))
    )
    (net (code "12") (name "Net-(LEDG05-PadDO)") (class "Default")
      (node (ref "LEDG05") (pin "DO") (pinfunction "DO_DO") (pintype "output"))
      (node (ref "LEDG06") (pin "DI") (pinfunction "DI_DI") (pintype "input"))
    )
    (net (code "13") (name "Net-(LEDG06-PadDO)") (class "Default")
      (node (ref "LEDG06") (pin "DO") (pinfunction "DO_DO") (pintype "output"))
      (node (ref "LEDG16") (pin "DI") (pinfunction "DI_DI") (pintype "input"))
    )
    (net (code "14") (name "Net-(LEDG07-PadDI)") (class "Default")
      (node (ref "LEDG07") (pin "DI") (pinfunction "DI_DI") (pintype "input"))
      (node (ref "LEDG17") (pin "DO") (pinfunction "DO_DO") (pintype "output"))
    )
    (net (code "15") (name "Net-(LEDG07-PadDO)") (class "Default")
      (node (ref "LEDG07") (pin "DO") (pinfunction "DO_DO") (pintype "output"))
      (node (ref "LEDG08") (pin "DI") (pinfunction "DI_DI") (pintype "input"))
    )
    (net (code "16") (name "Net-(LEDG08-PadDO)") (class "Default")
      (node (ref "LEDG08") (pin "DO") (pinfunction "DO_DO") (pintype "output"))
      (node (ref "LEDG18") (pin "DI") (pinfunction "DI_DI") (pintype "input"))
    )
    (net (code "17") (name "Net-(LEDG10-PadDO)") (class "Default")
      (node (ref "LEDG10") (pin "DO") (pinfunction "DO_DO") (pintype "output"))
      (node (ref "LEDG20") (pin "DI") (pinfunction "DI_DI") (pintype "input"))
    )
    (net (code "18") (name "Net-(LEDG11-PadDI)") (class "Default")
      (node (ref "LEDG11") (pin "DI") (pinfunction "DI_DI") (pintype "input"))
      (node (ref "LEDG21") (pin "DO") (pinfunction "DO_DO") (pintype "output"))
    )
    (net (code "19") (name "Net-(LEDG12-PadDO)") (class "Default")
      (node (ref "LEDG12") (pin "DO") (pinfunction "DO_DO") (pintype "output"))
      (node (ref "LEDG22") (pin "DI") (pinfunction "DI_DI") (pintype "input"))
    )
    (net (code "20") (name "Net-(LEDG13-PadDI)") (class "Default")
      (node (ref "LEDG13") (pin "DI") (pinfunction "DI_DI") (pintype "input"))
      (node (ref "LEDG23") (pin "DO") (pinfunction "DO_DO") (pintype "output"))
    )
    (net (code "21") (name "Net-(LEDG14-PadDO)") (class "Default")
      (node (ref "LEDG14") (pin "DO") (pinfunction "DO_DO") (pintype "output"))
      (node (ref "LEDG24") (pin "DI") (pinfunction "DI_DI") (pintype "input"))
    )
    (net (code "22") (name "Net-(LEDG15-PadDI)") (class "Default")
      (node (ref "LEDG15") (pin "DI") (pinfunction "DI_DI") (pintype "input"))
      (node (ref "LEDG25") (pin "DO") (pinfunction "DO_DO") (pintype "output"))
    )
    (net (code "23") (name "Net-(LEDG16-PadDO)") (class "Default")
      (node (ref "LEDG16") (pin "DO") (pinfunction "DO_DO") (pintype "output"))
      (node (ref "LEDG26") (pin "DI") (pinfunction "DI_DI") (pintype "input"))
    )
    (net (code "24") (name "Net-(LEDG17-PadDI)") (class "Default")
      (node (ref "LEDG17") (pin "DI") (pinfunction "DI_DI") (pintype "input"))
      (node (ref "LEDG27") (pin "DO") (pinfunction "DO_DO") (pintype "output"))
    )
    (net (code "25") (name "Net-(LEDG18-PadDO)") (class "Default")
      (node (ref "LEDG18") (pin "DO") (pinfunction "DO_DO") (pintype "output"))
      (node (ref "LEDG28") (pin "DI") (pinfunction "DI_DI") (pintype "input"))
    )
    (net (code "26") (name "Net-(LEDG20-PadDO)") (class "Default")
      (node (ref "LEDG20") (pin "DO") (pinfunction "DO_DO") (pintype "output"))
      (node (ref "LEDG30") (pin "DI") (pinfunction "DI_DI") (pintype "input"))
    )
    (net (code "27") (name "Net-(LEDG21-PadDI)") (class "Default")
      (node (ref "LEDG21") (pin "DI") (pinfunction "DI_DI") (pintype "input"))
      (node (ref "LEDG31") (pin "DO") (pinfunction "DO_DO") (pintype "output"))
    )
    (net (code "28") (name "Net-(LEDG22-PadDO)") (class "Default")
      (node (ref "LEDG22") (pin "DO") (pinfunction "DO_DO") (pintype "output"))
      (node (ref "LEDG32") (pin "DI") (pinfunction "DI_DI") (pintype "input"))
    )
    (net (code "29") (name "Net-(LEDG23-PadDI)") (class "Default")
      (node (ref "LEDG23") (pin "DI") (pinfunction "DI_DI") (pintype "input"))
      (node (ref "LEDG33") (pin "DO") (pinfunction "DO_DO") (pintype "output"))
    )
    (net (code "30") (name "Net-(LEDG24-PadDO)") (class "Default")
      (node (ref "LEDG24") (pin "DO") (pinfunction "DO_DO") (pintype "output"))
      (node (ref "LEDG34") (pin "DI") (pinfunction "DI_DI") (pintype "input"))
    )
    (net (code "31") (name "Net-(LEDG25-PadDI)") (class "Default")
      (node (ref "LEDG25") (pin "DI") (pinfunction "DI_DI") (pintype "input"))
      (node (ref "LEDG35") (pin "DO") (pinfunction "DO_DO") (pintype "output"))
    )
    (net (code "32") (name "Net-(LEDG26-PadDO)") (class "Default")
      (node (ref "LEDG26") (pin "DO") (pinfunction "DO_DO") (pintype "output"))
      (node (ref "LEDG36") (pin "DI") (pinfunction "DI_DI") (pintype "input"))
    )
    (net (code "33") (name "Net-(LEDG27-PadDI)") (class "Default")
      (node (ref "LEDG27") (pin "DI") (pinfunction "DI_DI") (pintype "input"))
      (node (ref "LEDG37") (pin "DO") (pinfunction "DO_DO") (pintype "output"))
    )
    (net (code "34") (name "Net-(LEDG28-PadDO)") (class "Default")
      (node (ref "LEDG28") (pin "DO") (pinfunction "DO_DO") (pintype "output"))
      (node (ref "LEDG38") (pin "DI") (pinfunction "DI_DI") (pintype "input"))
    )
    (net (code "35") (name "Net-(LEDG30-PadDO)") (class "Default")
      (node (ref "LEDG30") (pin "DO") (pinfunction "DO_DO") (pintype "output"))
      (node (ref "LEDG40") (pin "DI") (pinfunction "DI_DI") (pintype "input"))
    )
    (net (code "36") (name "Net-(LEDG31-PadDI)") (class "Default")
      (node (ref "LEDG31") (pin "DI") (pinfunction "DI_DI") (pintype "input"))
      (node (ref "LEDG41") (pin "DO") (pinfunction "DO_DO") (pintype "output"))
    )
    (net (code "37") (name "Net-(LEDG32-PadDO)") (class "Default")
      (node (ref "LEDG32") (pin "DO") (pinfunction "DO_DO") (pintype "output"))
      (node (ref "LEDG42") (pin "DI") (pinfunction "DI_DI") (pintype "input"))
    )
    (net (code "38") (name "Net-(LEDG33-PadDI)") (class "Default")
      (node (ref "LEDG33") (pin "DI") (pinfunction "DI_DI") (pintype "input"))
      (node (ref "LEDG43") (pin "DO") (pinfunction "DO_DO") (pintype "output"))
    )
    (net (code "39") (name "Net-(LEDG34-PadDO)") (class "Default")
      (node (ref "LEDG34") (pin "DO") (pinfunction "DO_DO") (pintype "output"))
      (node (ref "LEDG44") (pin "DI") (pinfunction "DI_DI") (pintype "input"))
    )
    (net (code "40") (name "Net-(LEDG35-PadDI)") (class "Default")
      (node (ref "LEDG35") (pin "DI") (pinfunction "DI_DI") (pintype "input"))
      (node (ref "LEDG45") (pin "DO") (pinfunction "DO_DO") (pintype "output"))
    )
    (net (code "41") (name "Net-(LEDG36-PadDO)") (class "Default")
      (node (ref "LEDG36") (pin "DO") (pinfunction "DO_DO") (pintype "output"))
      (node (ref "LEDG46") (pin "DI") (pinfunction "DI_DI") (pintype "input"))
    )
    (net (code "42") (name "Net-(LEDG37-PadDI)") (class "Default")
      (node (ref "LEDG37") (pin "DI") (pinfunction "DI_DI") (pintype "input"))
      (node (ref "LEDG47") (pin "DO") (pinfunction "DO_DO") (pintype "output"))
    )
    (net (code "43") (name "Net-(LEDG38-PadDO)") (class "Default")
      (node (ref "LEDG38") (pin "DO") (pinfunction "DO_DO") (pintype "output"))
      (node (ref "LEDG48") (pin "DI") (pinfunction "DI_DI") (pintype "input"))
    )
    (net (code "44") (name "Net-(LEDG40-PadDO)") (class "Default")
      (node (ref "LEDG40") (pin "DO") (pinfunction "DO_DO") (pintype "output"))
      (node (ref "LEDG50") (pin "DI") (pinfunction "DI_DI") (pintype "input"))
    )
    (net (code "45") (name "Net-(LEDG41-PadDI)") (class "Default")
      (node (ref "LEDG41") (pin "DI") (pinfunction "DI_DI") (pintype "input"))
      (node (ref "LEDG51") (pin "DO") (pinfunction "DO_DO") (pintype "output"))
    )
    (net (code "46") (name "Net-(LEDG42-PadDO)") (class "Default")
      (node (ref "LEDG42") (pin "DO") (pinfunction "DO_DO") (pintype "output"))
      (node (ref "LEDG52") (pin "DI") (pinfunction "DI_DI") (pintype "input"))
    )
    (net (code "47") (name "Net-(LEDG43-PadDI)") (class "Default")
      (node (ref "LEDG43") (pin "DI") (pinfunction "DI_DI") (pintype "input"))
      (node (ref "LEDG53") (pin "DO") (pinfunction "DO_DO") (pintype "output"))
    )
    (net (code "48") (name "Net-(LEDG44-PadDO)") (class "Default")
      (node (ref "LEDG44") (pin "DO") (pinfunction "DO_DO") (pintype "output"))
      (node (ref "LEDG54") (pin "DI") (pinfunction "DI_DI") (pintype "input"))
    )
    (net (code "49") (name "Net-(LEDG45-PadDI)") (class "Default")
      (node (ref "LEDG45") (pin "DI") (pinfunction "DI_DI") (pintype "input"))
      (node (ref "LEDG55") (pin "DO") (pinfunction "DO_DO") (pintype "output"))
    )
    (net (code "50") (name "Net-(LEDG46-PadDO)") (class "Default")
      (node (ref "LEDG46") (pin "DO") (pinfunction "DO_DO") (pintype "output"))
      (node (ref "LEDG56") (pin "DI") (pinfunction "DI_DI") (pintype "input"))
    )
    (net (code "51") (name "Net-(LEDG47-PadDI)") (class "Default")
      (node (ref "LEDG47") (pin "DI") (pinfunction "DI_DI") (pintype "input"))
      (node (ref "LEDG57") (pin "DO") (pinfunction "DO_DO") (pintype "output"))
    )
    (net (code "52") (name "Net-(LEDG48-PadDO)") (class "Default")
      (node (ref "LEDG48") (pin "DO") (pinfunction "DO_DO") (pintype "output"))
      (node (ref "LEDG58") (pin "DI") (pinfunction "DI_DI") (pintype "input"))
    )
    (net (code "53") (name "Net-(LEDG50-PadDO)") (class "Default")
      (node (ref "LEDG50") (pin "DO") (pinfunction "DO_DO") (pintype "output"))
      (node (ref "LEDG60") (pin "DI") (pinfunction "DI_DI") (pintype "input"))
    )
    (net (code "54") (name "Net-(LEDG51-PadDI)") (class "Default")
      (node (ref "LEDG51") (pin "DI") (pinfunction "DI_DI") (pintype "input"))
      (node (ref "LEDG61") (pin "DO") (pinfunction "DO_DO") (pintype "output"))
    )
    (net (code "55") (name "Net-(LEDG52-PadDO)") (class "Default")
      (node (ref "LEDG52") (pin "DO") (pinfunction "DO_DO") (pintype "output"))
      (node (ref "LEDG62") (pin "DI") (pinfunction "DI_DI") (pintype "input"))
    )
    (net (code "56") (name "Net-(LEDG53-PadDI)") (class "Default")
      (node (ref "LEDG53") (pin "DI") (pinfunction "DI_DI") (pintype "input"))
      (node (ref "LEDG63") (pin "DO") (pinfunction "DO_DO") (pintype "output"))
    )
    (net (code "57") (name "Net-(LEDG54-PadDO)") (class "Default")
      (node (ref "LEDG54") (pin "DO") (pinfunction "DO_DO") (pintype "output"))
      (node (ref "LEDG64") (pin "DI") (pinfunction "DI_DI") (pintype "input"))
    )
    (net (code "58") (name "Net-(LEDG55-PadDI)") (class "Default")
      (node (ref "LEDG55") (pin "DI") (pinfunction "DI_DI") (pintype "input"))
      (node (ref "LEDG65") (pin "DO") (pinfunction "DO_DO") (pintype "output"))
    )
    (net (code "59") (name "Net-(LEDG56-PadDO)") (class "Default")
      (node (ref "LEDG56") (pin "DO") (pinfunction "DO_DO") (pintype "output"))
      (node (ref "LEDG66") (pin "DI") (pinfunction "DI_DI") (pintype "input"))
    )
    (net (code "60") (name "Net-(LEDG57-PadDI)") (class "Default")
      (node (ref "LEDG57") (pin "DI") (pinfunction "DI_DI") (pintype "input"))
      (node (ref "LEDG67") (pin "DO") (pinfunction "DO_DO") (pintype "output"))
    )
    (net (code "61") (name "Net-(LEDG58-PadDO)") (class "Default")
      (node (ref "LEDG58") (pin "DO") (pinfunction "DO_DO") (pintype "output"))
      (node (ref "LEDG68") (pin "DI") (pinfunction "DI_DI") (pintype "input"))
    )
    (net (code "62") (name "Net-(LEDG60-PadDO)") (class "Default")
      (node (ref "LEDG60") (pin "DO") (pinfunction "DO_DO") (pintype "output"))
      (node (ref "LEDG70") (pin "DI") (pinfunction "DI_DI") (pintype "input"))
    )
    (net (code "63") (name "Net-(LEDG61-PadDI)") (class "Default")
      (node (ref "LEDG61") (pin "DI") (pinfunction "DI_DI") (pintype "input"))
      (node (ref "LEDG71") (pin "DO") (pinfunction "DO_DO") (pintype "output"))
    )
    (net (code "64") (name "Net-(LEDG62-PadDO)") (class "Default")
      (node (ref "LEDG62") (pin "DO") (pinfunction "DO_DO") (pintype "output"))
      (node (ref "LEDG72") (pin "DI") (pinfunction "DI_DI") (pintype "input"))
    )
    (net (code "65") (name "Net-(LEDG63-PadDI)") (class "Default")
      (node (ref "LEDG63") (pin "DI") (pinfunction "DI_DI") (pintype "input"))
      (node (ref "LEDG73") (pin "DO") (pinfunction "DO_DO") (pintype "output"))
    )
    (net (code "66") (name "Net-(LEDG64-PadDO)") (class "Default")
      (node (ref "LEDG64") (pin "DO") (pinfunction "DO_DO") (pintype "output"))
      (node (ref "LEDG74") (pin "DI") (pinfunction "DI_DI") (pintype "input"))
    )
    (net (code "67") (name "Net-(LEDG65-PadDI)") (class "Default")
      (node (ref "LEDG65") (pin "DI") (pinfunction "DI_DI") (pintype "input"))
      (node (ref "LEDG75") (pin "DO") (pinfunction "DO_DO") (pintype "output"))
    )
    (net (code "68") (name "Net-(LEDG66-PadDO)") (class "Default")
      (node (ref "LEDG66") (pin "DO") (pinfunction "DO_DO") (pintype "output"))
      (node (ref "LEDG76") (pin "DI") (pinfunction "DI_DI") (pintype "input"))
    )
    (net (code "69") (name "Net-(LEDG67-PadDI)") (class "Default")
      (node (ref "LEDG67") (pin "DI") (pinfunction "DI_DI") (pintype "input"))
      (node (ref "LEDG77") (pin "DO") (pinfunction "DO_DO") (pintype "output"))
    )
    (net (code "70") (name "Net-(LEDG68-PadDO)") (class "Default")
      (node (ref "LEDG68") (pin "DO") (pinfunction "DO_DO") (pintype "output"))
      (node (ref "LEDG78") (pin "DI") (pinfunction "DI_DI") (pintype "input"))
    )
    (net (code "71") (name "Net-(LEDG70-PadDO)") (class "Default")
      (node (ref "LEDG70") (pin "DO") (pinfunction "DO_DO") (pintype "output"))
      (node (ref "LEDG80") (pin "DI") (pinfunction "DI_DI") (pintype "input"))
    )
    (net (code "72") (name "Net-(LEDG71-PadDI)") (class "Default")
      (node (ref "LEDG71") (pin "DI") (pinfunction "DI_DI") (pintype "input"))
      (node (ref "LEDG81") (pin "DO") (pinfunction "DO_DO") (pintype "output"))
    )
    (net (code "73") (name "Net-(LEDG72-PadDO)") (class "Default")
      (node (ref "LEDG72") (pin "DO") (pinfunction "DO_DO") (pintype "output"))
      (node (ref "LEDG82") (pin "DI") (pinfunction "DI_DI") (pintype "input"))
    )
    (net (code "74") (name "Net-(LEDG73-PadDI)") (class "Default")
      (node (ref "LEDG73") (pin "DI") (pinfunction "DI_DI") (pintype "input"))
      (node (ref "LEDG83") (pin "DO") (pinfunction "DO_DO") (pintype "output"))
    )
    (net (code "75") (name "Net-(LEDG74-PadDO)") (class "Default")
      (node (ref "LEDG74") (pin "DO") (pinfunction "DO_DO") (pintype "output"))
      (node (ref "LEDG84") (pin "DI") (pinfunction "DI_DI") (pintype "input"))
    )
    (net (code "76") (name "Net-(LEDG75-PadDI)") (class "Default")
      (node (ref "LEDG75") (pin "DI") (pinfunction "DI_DI") (pintype "input"))
      (node (ref "LEDG85") (pin "DO") (pinfunction "DO_DO") (pintype "output"))
    )
    (net (code "77") (name "Net-(LEDG76-PadDO)") (class "Default")
      (node (ref "LEDG76") (pin "DO") (pinfunction "DO_DO") (pintype "output"))
      (node (ref "LEDG86") (pin "DI") (pinfunction "DI_DI") (pintype "input"))
    )
    (net (code "78") (name "Net-(LEDG77-PadDI)") (class "Default")
      (node (ref "LEDG77") (pin "DI") (pinfunction "DI_DI") (pintype "input"))
      (node (ref "LEDG87") (pin "DO") (pinfunction "DO_DO") (pintype "output"))
    )
    (net (code "79") (name "Net-(LEDG78-PadDO)") (class "Default")
      (node (ref "LEDG78") (pin "DO") (pinfunction "DO_DO") (pintype "output"))
      (node (ref "LEDG88") (pin "DI") (pinfunction "DI_DI") (pintype "input"))
    )
    (net (code "80") (name "Net-(LEDG80-PadDO)") (class "Default")
      (node (ref "LEDG80") (pin "DO") (pinfunction "DO_DO") (pintype "output"))
      (node (ref "LEDG81") (pin "DI") (pinfunction "DI_DI") (pintype "input"))
    )
    (net (code "81") (name "Net-(LEDG82-PadDO)") (class "Default")
      (node (ref "LEDG82") (pin "DO") (pinfunction "DO_DO") (pintype "output"))
      (node (ref "LEDG83") (pin "DI") (pinfunction "DI_DI") (pintype "input"))
    )
    (net (code "82") (name "Net-(LEDG84-PadDO)") (class "Default")
      (node (ref "LEDG84") (pin "DO") (pinfunction "DO_DO") (pintype "output"))
      (node (ref "LEDG85") (pin "DI") (pinfunction "DI_DI") (pintype "input"))
    )
    (net (code "83") (name "Net-(LEDG86-PadDO)") (class "Default")
      (node (ref "LEDG86") (pin "DO") (pinfunction "DO_DO") (pintype "output"))
      (node (ref "LEDG87") (pin "DI") (pinfunction "DI_DI") (pintype "input"))
    )
    (net (code "84") (name "unconnected-(LEDG88-PadDO)") (class "Default")
      (node (ref "LEDG88") (pin "DO") (pinfunction "DO_DO") (pintype "output"))
    )
  )
)
